# HDMI.net
KiCad netlist of a schematic drawn in Altium Designer
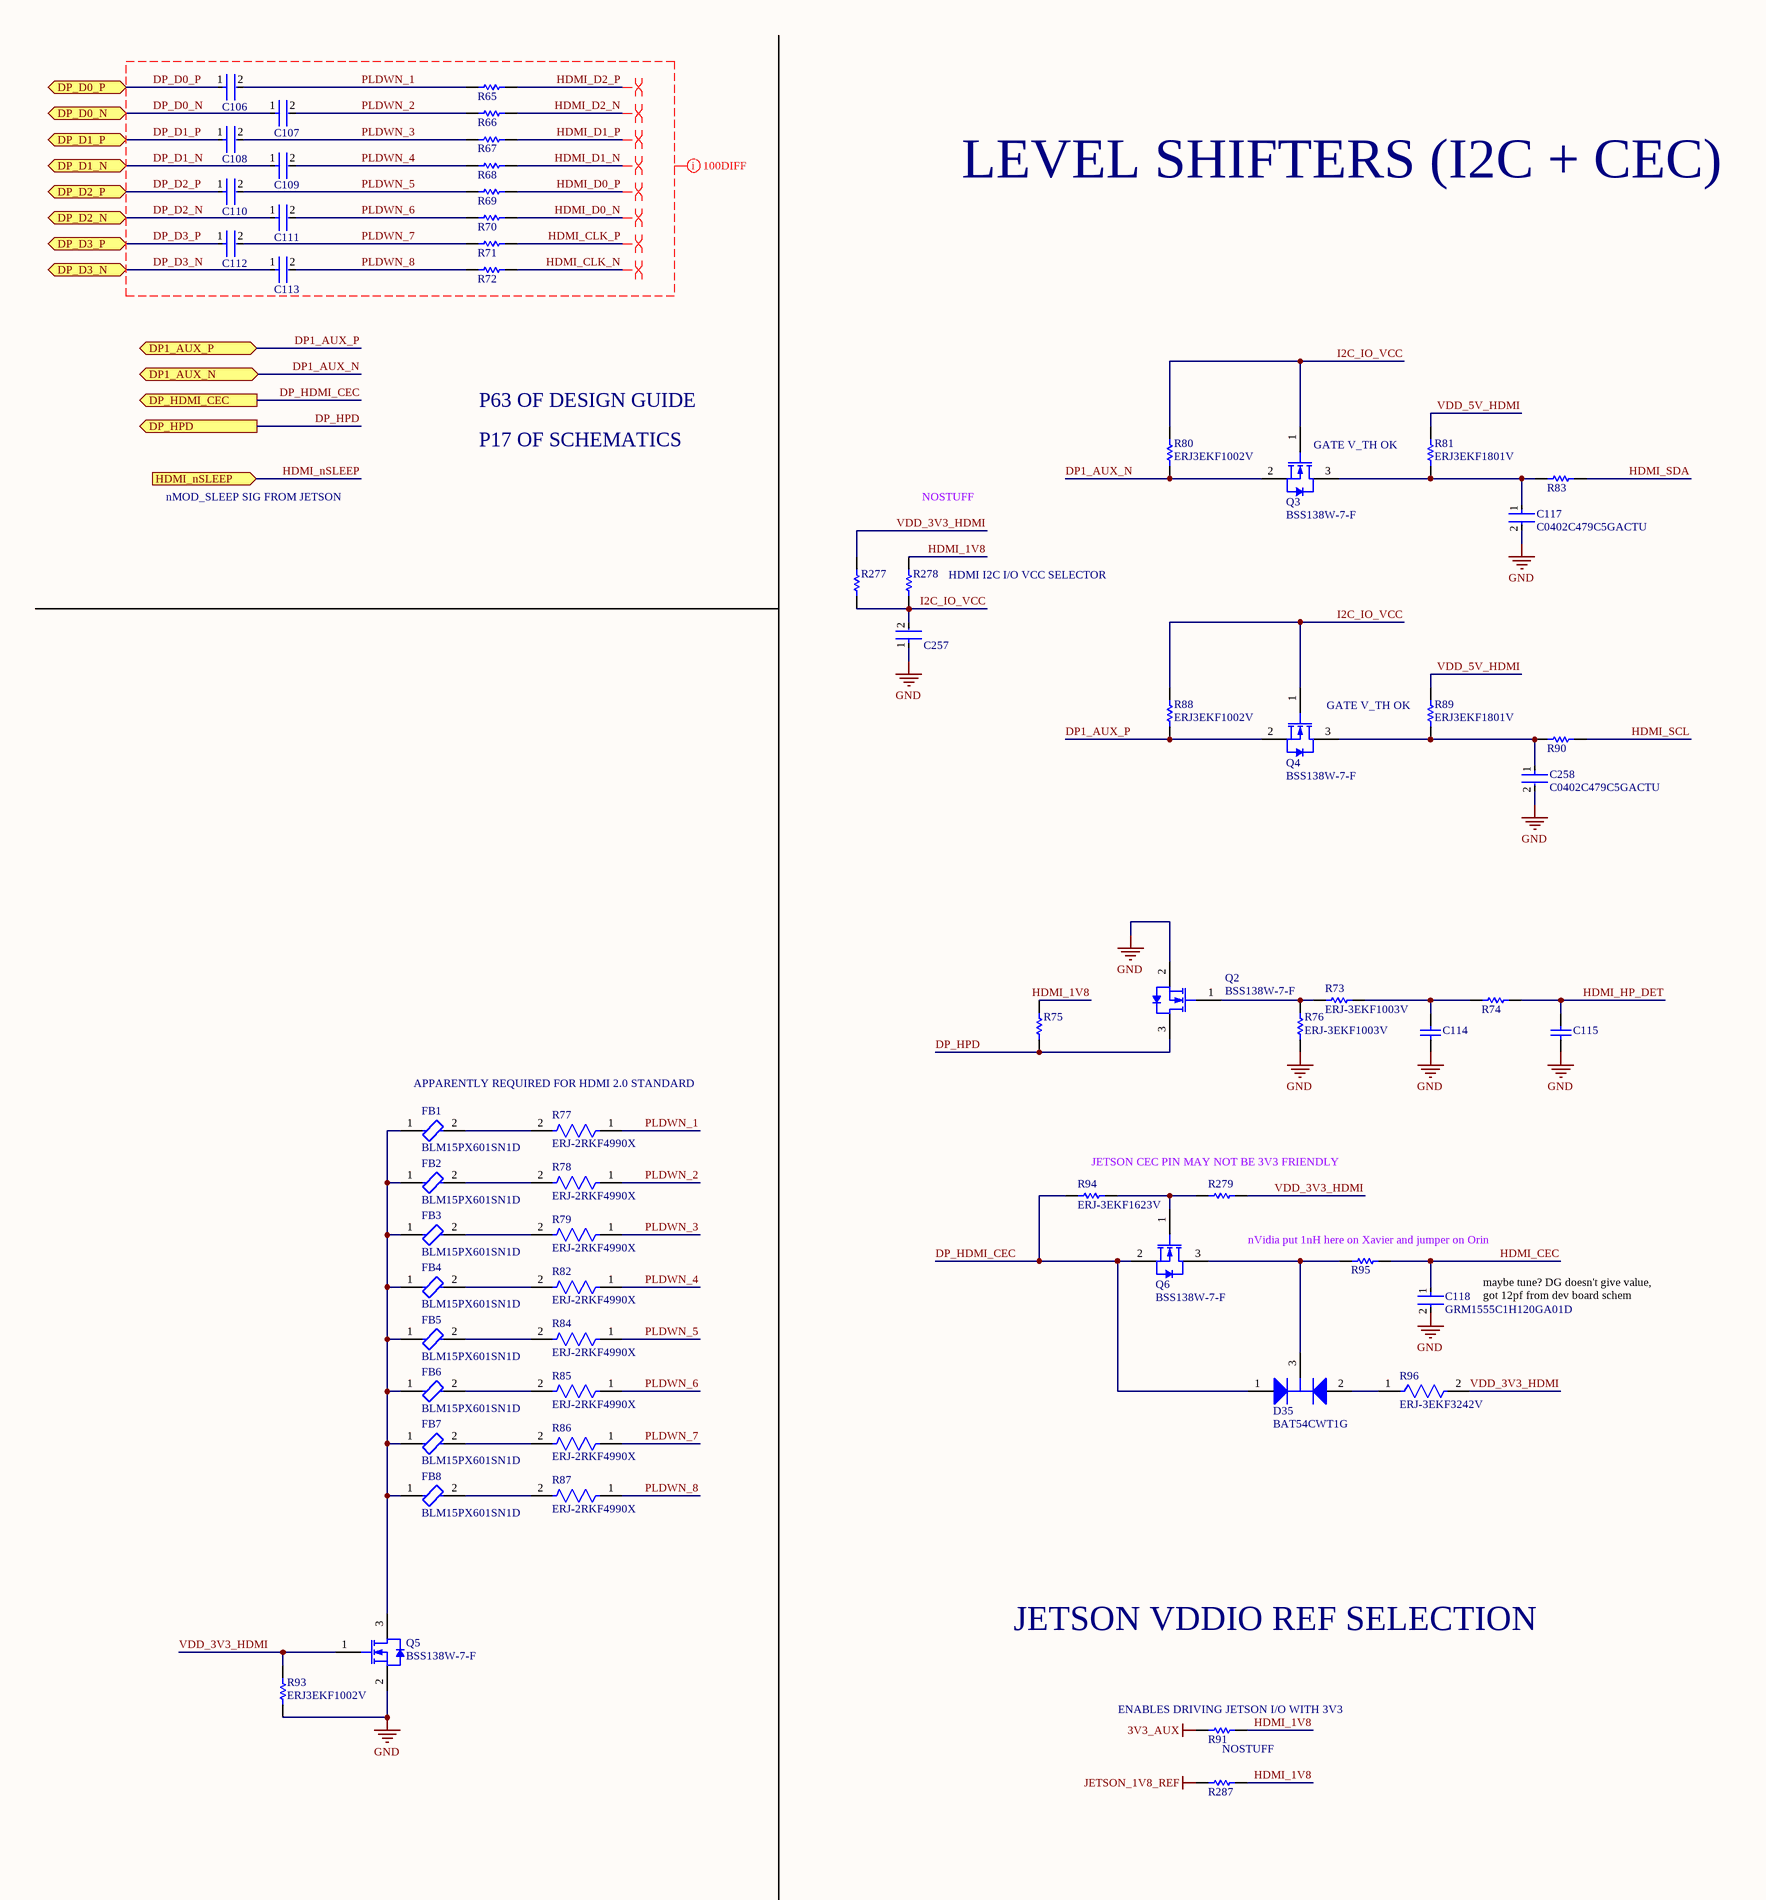
[diagram p0: HDMI.SchDoc, left]
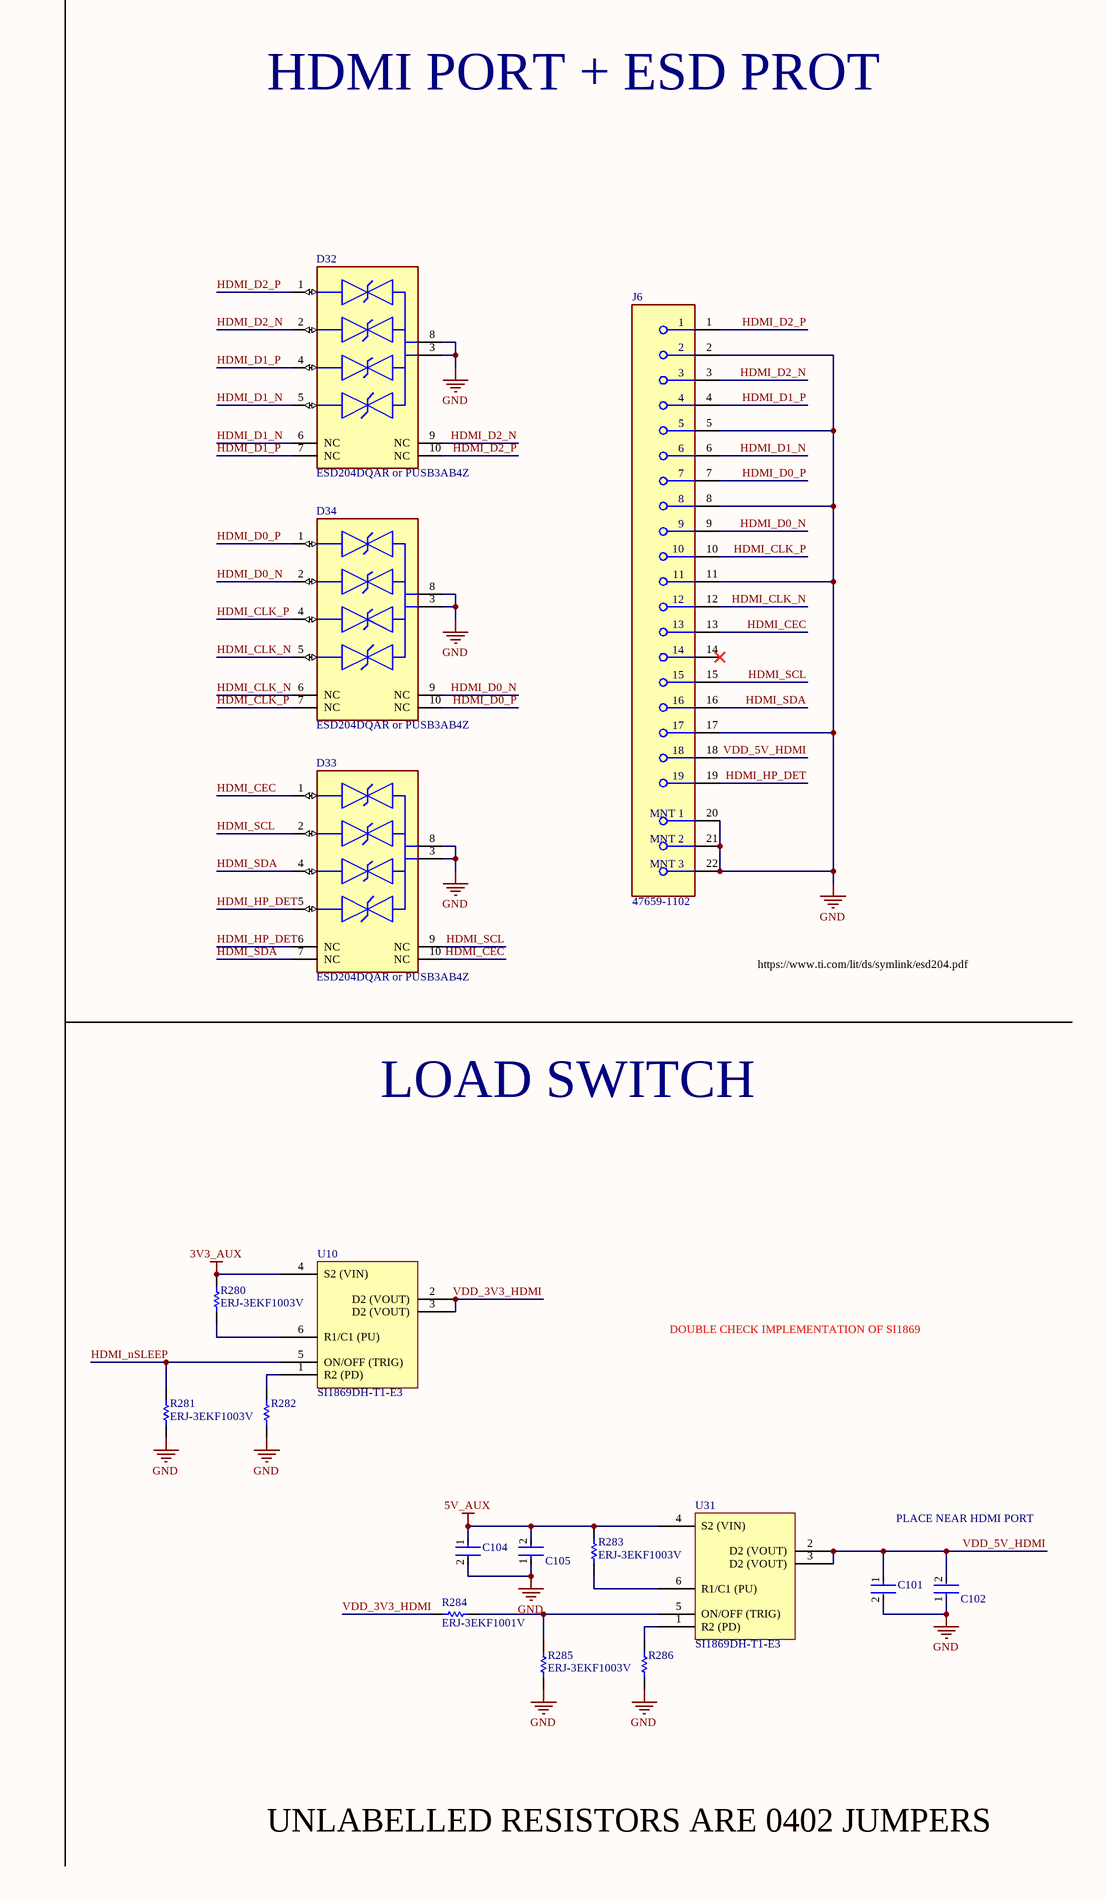
[diagram p1: HDMI.SchDoc, right]

(export (version "E")
  (design (tool "Eeschema 10.0.6"))
  (components
    (comp (ref "C101")
      (value "GRM188R60J106ME47D")
      (footprint "FP-GRM188-0_1-e0_2_0_55-IPC_A")
      (description "Chip Multilayer Ceramic Capacitors for General Purpose, 0603, 10uF, X5R, 15%, 20%, 6.3V")
      (fields (field (name "VOLTAGE") "6.3V") (field (name "TOLERANCE") "20%"))
      (libsource (lib "Altium Content Vault") (part "02cd4be3c70576c341d710602a673aa"))
    )
    (comp (ref "C102")
      (value "C1005X7R1H104K050BB")
      (footprint "FP-C1005-050-0_05-IPC_C")
      (description "Multilayer Ceramic Capacitors 100nF ±10% 50V X7R SMD 0402")
      (fields (field (name "VOLTAGE") "50V") (field (name "TOLERANCE") "10%"))
      (libsource (lib "Altium Content Vault") (part "b4654b650e69147ec39a6b967a45e02"))
    )
    (comp (ref "C104")
      (value "GRM188R60J106ME47D")
      (footprint "FP-GRM188-0_1-e0_2_0_55-IPC_A")
      (description "Chip Multilayer Ceramic Capacitors for General Purpose, 0603, 10uF, X5R, 15%, 20%, 6.3V")
      (fields (field (name "VOLTAGE") "6.3V") (field (name "TOLERANCE") "20%"))
      (libsource (lib "Altium Content Vault") (part "02cd4be3c70576c341d710602a673aa"))
    )
    (comp (ref "C105")
      (value "C1005X7R1H104K050BB")
      (footprint "FP-C1005-050-0_05-IPC_C")
      (description "Multilayer Ceramic Capacitors 100nF ±10% 50V X7R SMD 0402")
      (fields (field (name "VOLTAGE") "50V") (field (name "TOLERANCE") "10%"))
      (libsource (lib "Altium Content Vault") (part "b4654b650e69147ec39a6b967a45e02"))
    )
    (comp (ref "C106")
      (value "C1005X7R1H104K050BB")
      (footprint "FP-C1005-050-0_05-IPC_C")
      (description "Multilayer Ceramic Capacitors 100nF ±10% 50V X7R SMD 0402")
      (fields (field (name "VOLTAGE") "50V") (field (name "TOLERANCE") "10%"))
      (libsource (lib "Altium Content Vault") (part "b4654b650e69147ec39a6b967a45e02"))
    )
    (comp (ref "C107")
      (value "C1005X7R1H104K050BB")
      (footprint "FP-C1005-050-0_05-IPC_C")
      (description "Multilayer Ceramic Capacitors 100nF ±10% 50V X7R SMD 0402")
      (fields (field (name "VOLTAGE") "50V") (field (name "TOLERANCE") "10%"))
      (libsource (lib "Altium Content Vault") (part "b4654b650e69147ec39a6b967a45e02"))
    )
    (comp (ref "C108")
      (value "C1005X7R1H104K050BB")
      (footprint "FP-C1005-050-0_05-IPC_C")
      (description "Multilayer Ceramic Capacitors 100nF ±10% 50V X7R SMD 0402")
      (fields (field (name "VOLTAGE") "50V") (field (name "TOLERANCE") "10%"))
      (libsource (lib "Altium Content Vault") (part "b4654b650e69147ec39a6b967a45e02"))
    )
    (comp (ref "C109")
      (value "C1005X7R1H104K050BB")
      (footprint "FP-C1005-050-0_05-IPC_C")
      (description "Multilayer Ceramic Capacitors 100nF ±10% 50V X7R SMD 0402")
      (fields (field (name "VOLTAGE") "50V") (field (name "TOLERANCE") "10%"))
      (libsource (lib "Altium Content Vault") (part "b4654b650e69147ec39a6b967a45e02"))
    )
    (comp (ref "C110")
      (value "C1005X7R1H104K050BB")
      (footprint "FP-C1005-050-0_05-IPC_C")
      (description "Multilayer Ceramic Capacitors 100nF ±10% 50V X7R SMD 0402")
      (fields (field (name "VOLTAGE") "50V") (field (name "TOLERANCE") "10%"))
      (libsource (lib "Altium Content Vault") (part "b4654b650e69147ec39a6b967a45e02"))
    )
    (comp (ref "C111")
      (value "C1005X7R1H104K050BB")
      (footprint "FP-C1005-050-0_05-IPC_C")
      (description "Multilayer Ceramic Capacitors 100nF ±10% 50V X7R SMD 0402")
      (fields (field (name "VOLTAGE") "50V") (field (name "TOLERANCE") "10%"))
      (libsource (lib "Altium Content Vault") (part "b4654b650e69147ec39a6b967a45e02"))
    )
    (comp (ref "C112")
      (value "C1005X7R1H104K050BB")
      (footprint "FP-C1005-050-0_05-IPC_C")
      (description "Multilayer Ceramic Capacitors 100nF ±10% 50V X7R SMD 0402")
      (fields (field (name "VOLTAGE") "50V") (field (name "TOLERANCE") "10%"))
      (libsource (lib "Altium Content Vault") (part "b4654b650e69147ec39a6b967a45e02"))
    )
    (comp (ref "C113")
      (value "C1005X7R1H104K050BB")
      (footprint "FP-C1005-050-0_05-IPC_C")
      (description "Multilayer Ceramic Capacitors 100nF ±10% 50V X7R SMD 0402")
      (fields (field (name "VOLTAGE") "50V") (field (name "TOLERANCE") "10%"))
      (libsource (lib "Altium Content Vault") (part "b4654b650e69147ec39a6b967a45e02"))
    )
    (comp (ref "C114")
      (value "C0402C221K5RAC7867")
      (footprint "CAPC1005X60X30NL05T10")
      (fields (field (name "MANUFACTURER") "Kemet"))
      (libsource (lib "Altium Content Vault") (part "CAP"))
    )
    (comp (ref "C115")
      (value "C0402C221K5RAC7867")
      (footprint "CAPC1005X60X30NL05T10")
      (fields (field (name "MANUFACTURER") "Kemet"))
      (libsource (lib "Altium Content Vault") (part "CAP"))
    )
    (comp (ref "C117")
      (value "C0402C479C5GACTU")
      (footprint "FP-C0402-BB-MFG")
      (description "CAP CER 4.7PF 50V NP0 0402")
      (fields
        (field (name "TOLERANCE") "0.25 pF")
        (field (name "OCTOPART") "https://octopart.com/c0402c479c5gactu-kemet-9144199")
      )
      (libsource (lib "Altium Content Vault") (part "b4654b650e69147ec39a6b967a45e02"))
    )
    (comp (ref "C118")
      (value "GRM1555C1H120GA01D")
      (footprint "FP-GRM155-0_05-MFG")
      (description "CAP CER 12PF 50V C0G/NP0 0402")
      (fields (field (name "TOLERANCE") "2%") (field (name "VOLTAGE") "50V"))
      (libsource (lib "Altium Content Vault") (part "b4654b650e69147ec39a6b967a45e02"))
    )
    (comp (ref "C257")
      (value "C1005X7R1H104K050BB")
      (footprint "FP-C1005-050-0_05-IPC_C")
      (description "Multilayer Ceramic Capacitors 100nF ±10% 50V X7R SMD 0402")
      (fields (field (name "VOLTAGE") "50V") (field (name "TOLERANCE") "10%"))
      (libsource (lib "Altium Content Vault") (part "b4654b650e69147ec39a6b967a45e02"))
    )
    (comp (ref "C258")
      (value "C0402C479C5GACTU")
      (footprint "FP-C0402-BB-MFG")
      (description "CAP CER 4.7PF 50V NP0 0402")
      (fields
        (field (name "TOLERANCE") "0.25 pF")
        (field (name "OCTOPART") "https://octopart.com/c0402c479c5gactu-kemet-9144199")
      )
      (libsource (lib "Altium Content Vault") (part "b4654b650e69147ec39a6b967a45e02"))
    )
    (comp (ref "D32")
      (value "ESD204DQAR or PUSB3AB4Z")
      (footprint "FP-DQA0010A-MFG")
      (description "4-CHANNEL LOW-CAPACITANCE SURGE")
      (fields
        (field (name "MANUFACTURER") "Texas Instruments")
        (field (name "OCTOPART") "https://octopart.com/esd204dqar-texas+instruments-89917476")
      )
      (libsource (lib "Altium Content Vault") (part "1465e58c1818c7767b55926832f0bf5"))
    )
    (comp (ref "D33")
      (value "ESD204DQAR or PUSB3AB4Z")
      (footprint "FP-DQA0010A-MFG")
      (description "4-CHANNEL LOW-CAPACITANCE SURGE")
      (fields
        (field (name "MANUFACTURER") "Texas Instruments")
        (field (name "OCTOPART") "https://octopart.com/esd204dqar-texas+instruments-89917476")
      )
      (libsource (lib "Altium Content Vault") (part "1465e58c1818c7767b55926832f0bf5"))
    )
    (comp (ref "D34")
      (value "ESD204DQAR or PUSB3AB4Z")
      (footprint "FP-DQA0010A-MFG")
      (description "4-CHANNEL LOW-CAPACITANCE SURGE")
      (fields
        (field (name "MANUFACTURER") "Texas Instruments")
        (field (name "OCTOPART") "https://octopart.com/esd204dqar-texas+instruments-89917476")
      )
      (libsource (lib "Altium Content Vault") (part "1465e58c1818c7767b55926832f0bf5"))
    )
    (comp (ref "D35")
      (value "BAT54CWT1G")
      (footprint "ONSC-SOT-323-3-419-04_V")
      (description "Dual Series Cathode Schottky Barrier Diodes, 3-Pin SOT-323, Pb-Free, Tape and Reel")
      (fields (field (name "MANUFACTURER") "On Semiconductor"))
      (libsource (lib "Altium Content Vault") (part "ONSC-D-A1A2K3-3"))
    )
    (comp (ref "FB1")
      (value "BLM15PX601SN1D")
      (footprint "FP-BLM15-0_05-MFG")
      (description "Chip Ferrite Bead, 0402, 600Ω @ 100MHz, 0.23Ω, 25%, 900mA")
      (fields (field (name "TOLERANCE") "25%"))
      (libsource (lib "Altium Content Vault") (part "5f30dd21d616792df468990f7003faa"))
    )
    (comp (ref "FB2")
      (value "BLM15PX601SN1D")
      (footprint "FP-BLM15-0_05-MFG")
      (description "Chip Ferrite Bead, 0402, 600Ω @ 100MHz, 0.23Ω, 25%, 900mA")
      (fields (field (name "TOLERANCE") "25%"))
      (libsource (lib "Altium Content Vault") (part "5f30dd21d616792df468990f7003faa"))
    )
    (comp (ref "FB3")
      (value "BLM15PX601SN1D")
      (footprint "FP-BLM15-0_05-MFG")
      (description "Chip Ferrite Bead, 0402, 600Ω @ 100MHz, 0.23Ω, 25%, 900mA")
      (fields (field (name "TOLERANCE") "25%"))
      (libsource (lib "Altium Content Vault") (part "5f30dd21d616792df468990f7003faa"))
    )
    (comp (ref "FB4")
      (value "BLM15PX601SN1D")
      (footprint "FP-BLM15-0_05-MFG")
      (description "Chip Ferrite Bead, 0402, 600Ω @ 100MHz, 0.23Ω, 25%, 900mA")
      (fields (field (name "TOLERANCE") "25%"))
      (libsource (lib "Altium Content Vault") (part "5f30dd21d616792df468990f7003faa"))
    )
    (comp (ref "FB5")
      (value "BLM15PX601SN1D")
      (footprint "FP-BLM15-0_05-MFG")
      (description "Chip Ferrite Bead, 0402, 600Ω @ 100MHz, 0.23Ω, 25%, 900mA")
      (fields (field (name "TOLERANCE") "25%"))
      (libsource (lib "Altium Content Vault") (part "5f30dd21d616792df468990f7003faa"))
    )
    (comp (ref "FB6")
      (value "BLM15PX601SN1D")
      (footprint "FP-BLM15-0_05-MFG")
      (description "Chip Ferrite Bead, 0402, 600Ω @ 100MHz, 0.23Ω, 25%, 900mA")
      (fields (field (name "TOLERANCE") "25%"))
      (libsource (lib "Altium Content Vault") (part "5f30dd21d616792df468990f7003faa"))
    )
    (comp (ref "FB7")
      (value "BLM15PX601SN1D")
      (footprint "FP-BLM15-0_05-MFG")
      (description "Chip Ferrite Bead, 0402, 600Ω @ 100MHz, 0.23Ω, 25%, 900mA")
      (fields (field (name "TOLERANCE") "25%"))
      (libsource (lib "Altium Content Vault") (part "5f30dd21d616792df468990f7003faa"))
    )
    (comp (ref "FB8")
      (value "BLM15PX601SN1D")
      (footprint "FP-BLM15-0_05-MFG")
      (description "Chip Ferrite Bead, 0402, 600Ω @ 100MHz, 0.23Ω, 25%, 900mA")
      (fields (field (name "TOLERANCE") "25%"))
      (libsource (lib "Altium Content Vault") (part "5f30dd21d616792df468990f7003faa"))
    )
    (comp (ref "J6")
      (value "47659-1102")
      (footprint "FP-47659-1102-MFG")
      (description "HDMI REC.VERTICAL SMT TYPE W/HEI")
      (libsource (lib "Altium Content Vault") (part "60e05bcc1364a128ef07df4509dd673"))
    )
    (comp (ref "Q2")
      (value "BSS138W-7-F")
      (footprint "DIOD-SOT323-3_V")
      (fields (field (name "MANUFACTURER") "DiodesIncorporated"))
      (libsource (lib "Altium Content Vault") (part "NEMOS-GSD-3"))
    )
    (comp (ref "Q3")
      (value "BSS138W-7-F")
      (footprint "DIOD-SOT323-3_V")
      (fields (field (name "MANUFACTURER") "DiodesIncorporated"))
      (libsource (lib "Altium Content Vault") (part "NEMOS-GSD-3"))
    )
    (comp (ref "Q4")
      (value "BSS138W-7-F")
      (footprint "DIOD-SOT323-3_V")
      (fields (field (name "MANUFACTURER") "DiodesIncorporated"))
      (libsource (lib "Altium Content Vault") (part "NEMOS-GSD-3"))
    )
    (comp (ref "Q5")
      (value "BSS138W-7-F")
      (footprint "DIOD-SOT323-3_V")
      (fields (field (name "MANUFACTURER") "DiodesIncorporated"))
      (libsource (lib "Altium Content Vault") (part "NEMOS-GSD-3"))
    )
    (comp (ref "Q6")
      (value "BSS138W-7-F")
      (footprint "DIOD-SOT323-3_V")
      (fields (field (name "MANUFACTURER") "DiodesIncorporated"))
      (libsource (lib "Altium Content Vault") (part "NEMOS-GSD-3"))
    )
    (comp (ref "R65")
      (value "0402 JUMPER")
      (footprint "RESC1005X40X25ML05T05")
      (description "READ THE NAME")
      (libsource (lib "Space Concordia") (part "CMP-009-00206-2"))
    )
    (comp (ref "R66")
      (value "0402 JUMPER")
      (footprint "RESC1005X40X25ML05T05")
      (description "READ THE NAME")
      (libsource (lib "Space Concordia") (part "CMP-009-00206-2"))
    )
    (comp (ref "R67")
      (value "0402 JUMPER")
      (footprint "RESC1005X40X25ML05T05")
      (description "READ THE NAME")
      (libsource (lib "Space Concordia") (part "CMP-009-00206-2"))
    )
    (comp (ref "R68")
      (value "0402 JUMPER")
      (footprint "RESC1005X40X25ML05T05")
      (description "READ THE NAME")
      (libsource (lib "Space Concordia") (part "CMP-009-00206-2"))
    )
    (comp (ref "R69")
      (value "0402 JUMPER")
      (footprint "RESC1005X40X25ML05T05")
      (description "READ THE NAME")
      (libsource (lib "Space Concordia") (part "CMP-009-00206-2"))
    )
    (comp (ref "R70")
      (value "0402 JUMPER")
      (footprint "RESC1005X40X25ML05T05")
      (description "READ THE NAME")
      (libsource (lib "Space Concordia") (part "CMP-009-00206-2"))
    )
    (comp (ref "R71")
      (value "0402 JUMPER")
      (footprint "RESC1005X40X25ML05T05")
      (description "READ THE NAME")
      (libsource (lib "Space Concordia") (part "CMP-009-00206-2"))
    )
    (comp (ref "R72")
      (value "0402 JUMPER")
      (footprint "RESC1005X40X25ML05T05")
      (description "READ THE NAME")
      (libsource (lib "Space Concordia") (part "CMP-009-00206-2"))
    )
    (comp (ref "R73")
      (value "ERJ-3EKF1003V")
      (footprint "RESC1608X55X30ML15T15")
      (fields (field (name "MANUFACTURER") "Panasonic"))
      (libsource (lib "Altium Content Vault") (part "RES"))
    )
    (comp (ref "R74")
      (value "0402 JUMPER")
      (footprint "RESC1005X40X25ML05T05")
      (description "READ THE NAME")
      (libsource (lib "Space Concordia") (part "CMP-009-00206-2"))
    )
    (comp (ref "R75")
      (value "ERJ3EKF1002V")
      (footprint "RESC1609X55X30LL15T15")
      (description "Chip Resistor, 10 KOhm, +/- 1%, 0.1 W, -55 to 155 degC, 0603 (1608 Metric), RoHS, Tape and Reel")
      (fields (field (name "TOLERANCE") "1%") (field (name "MANUFACTURER") "Panasonic"))
      (libsource (lib "Altium Content Vault") (part "RES-2"))
    )
    (comp (ref "R76")
      (value "ERJ-3EKF1003V")
      (footprint "RESC1608X55X30ML15T15")
      (fields (field (name "MANUFACTURER") "Panasonic"))
      (libsource (lib "Altium Content Vault") (part "RES"))
    )
    (comp (ref "R77")
      (value "ERJ-2RKF4990X")
      (footprint "FP-ERJ2RK-MFG")
      (description "RES SMD 499 OHM 1% 1/10W 0402")
      (fields (field (name "TOLERANCE") "1%"))
      (libsource (lib "Altium Content Vault") (part "1029c3af85768c4190bb7ad29bc67b5"))
    )
    (comp (ref "R78")
      (value "ERJ-2RKF4990X")
      (footprint "FP-ERJ2RK-MFG")
      (description "RES SMD 499 OHM 1% 1/10W 0402")
      (fields (field (name "TOLERANCE") "1%"))
      (libsource (lib "Altium Content Vault") (part "1029c3af85768c4190bb7ad29bc67b5"))
    )
    (comp (ref "R79")
      (value "ERJ-2RKF4990X")
      (footprint "FP-ERJ2RK-MFG")
      (description "RES SMD 499 OHM 1% 1/10W 0402")
      (fields (field (name "TOLERANCE") "1%"))
      (libsource (lib "Altium Content Vault") (part "1029c3af85768c4190bb7ad29bc67b5"))
    )
    (comp (ref "R80")
      (value "ERJ3EKF1002V")
      (footprint "RESC1609X55X30LL15T15")
      (description "Chip Resistor, 10 KOhm, +/- 1%, 0.1 W, -55 to 155 degC, 0603 (1608 Metric), RoHS, Tape and Reel")
      (fields (field (name "TOLERANCE") "1%") (field (name "MANUFACTURER") "Panasonic"))
      (libsource (lib "Altium Content Vault") (part "RES-2"))
    )
    (comp (ref "R81")
      (value "ERJ3EKF1801V")
      (footprint "RESC1608X55X30LL15T15")
      (description "MODIFIED P/N")
      (fields (field (name "MANUFACTURER") "Panasonic") (field (name "PART NUMBER") "ERJ3EKF2701V"))
      (libsource (lib "Altium Content Vault") (part "RES"))
    )
    (comp (ref "R82")
      (value "ERJ-2RKF4990X")
      (footprint "FP-ERJ2RK-MFG")
      (description "RES SMD 499 OHM 1% 1/10W 0402")
      (fields (field (name "TOLERANCE") "1%"))
      (libsource (lib "Altium Content Vault") (part "1029c3af85768c4190bb7ad29bc67b5"))
    )
    (comp (ref "R83")
      (value "0402 JUMPER")
      (footprint "RESC1005X40X25ML05T05")
      (description "READ THE NAME")
      (libsource (lib "Space Concordia") (part "CMP-009-00206-2"))
    )
    (comp (ref "R84")
      (value "ERJ-2RKF4990X")
      (footprint "FP-ERJ2RK-MFG")
      (description "RES SMD 499 OHM 1% 1/10W 0402")
      (fields (field (name "TOLERANCE") "1%"))
      (libsource (lib "Altium Content Vault") (part "1029c3af85768c4190bb7ad29bc67b5"))
    )
    (comp (ref "R85")
      (value "ERJ-2RKF4990X")
      (footprint "FP-ERJ2RK-MFG")
      (description "RES SMD 499 OHM 1% 1/10W 0402")
      (fields (field (name "TOLERANCE") "1%"))
      (libsource (lib "Altium Content Vault") (part "1029c3af85768c4190bb7ad29bc67b5"))
    )
    (comp (ref "R86")
      (value "ERJ-2RKF4990X")
      (footprint "FP-ERJ2RK-MFG")
      (description "RES SMD 499 OHM 1% 1/10W 0402")
      (fields (field (name "TOLERANCE") "1%"))
      (libsource (lib "Altium Content Vault") (part "1029c3af85768c4190bb7ad29bc67b5"))
    )
    (comp (ref "R87")
      (value "ERJ-2RKF4990X")
      (footprint "FP-ERJ2RK-MFG")
      (description "RES SMD 499 OHM 1% 1/10W 0402")
      (fields (field (name "TOLERANCE") "1%"))
      (libsource (lib "Altium Content Vault") (part "1029c3af85768c4190bb7ad29bc67b5"))
    )
    (comp (ref "R88")
      (value "ERJ3EKF1002V")
      (footprint "RESC1609X55X30LL15T15")
      (description "Chip Resistor, 10 KOhm, +/- 1%, 0.1 W, -55 to 155 degC, 0603 (1608 Metric), RoHS, Tape and Reel")
      (fields (field (name "TOLERANCE") "1%") (field (name "MANUFACTURER") "Panasonic"))
      (libsource (lib "Altium Content Vault") (part "RES-2"))
    )
    (comp (ref "R89")
      (value "ERJ3EKF1801V")
      (footprint "RESC1608X55X30LL15T15")
      (description "MODIFIED P/N")
      (fields (field (name "MANUFACTURER") "Panasonic") (field (name "PART NUMBER") "ERJ3EKF2701V"))
      (libsource (lib "Altium Content Vault") (part "RES"))
    )
    (comp (ref "R90")
      (value "0402 JUMPER")
      (footprint "RESC1005X40X25ML05T05")
      (description "READ THE NAME")
      (libsource (lib "Space Concordia") (part "CMP-009-00206-2"))
    )
    (comp (ref "R91")
      (value "0402 JUMPER")
      (footprint "RESC1005X40X25ML05T05")
      (description "READ THE NAME")
      (libsource (lib "Space Concordia") (part "CMP-009-00206-2"))
    )
    (comp (ref "R93")
      (value "ERJ3EKF1002V")
      (footprint "RESC1609X55X30LL15T15")
      (description "Chip Resistor, 10 KOhm, +/- 1%, 0.1 W, -55 to 155 degC, 0603 (1608 Metric), RoHS, Tape and Reel")
      (fields (field (name "TOLERANCE") "1%") (field (name "MANUFACTURER") "Panasonic"))
      (libsource (lib "Altium Content Vault") (part "RES-2"))
    )
    (comp (ref "R94")
      (value "ERJ-3EKF1623V")
      (footprint "RESC1608X55X30ML15T15")
      (fields (field (name "MANUFACTURER") "Panasonic"))
      (libsource (lib "Altium Content Vault") (part "RES"))
    )
    (comp (ref "R95")
      (value "0402 JUMPER")
      (footprint "RESC1005X40X25ML05T05")
      (description "READ THE NAME")
      (libsource (lib "Space Concordia") (part "CMP-009-00206-2"))
    )
    (comp (ref "R96")
      (value "ERJ-3EKF3242V")
      (footprint "FP-ERJ3EK-MFG")
      (description "RES SMD 32.4K OHM 1% 1/10W 0603")
      (fields (field (name "TOLERANCE") "1%"))
      (libsource (lib "Altium Content Vault") (part "1029c3af85768c4190bb7ad29bc67b5"))
    )
    (comp (ref "R277")
      (value "0402 JUMPER")
      (footprint "RESC1005X40X25ML05T05")
      (description "READ THE NAME")
      (libsource (lib "Space Concordia") (part "CMP-009-00206-2"))
    )
    (comp (ref "R278")
      (value "0402 JUMPER")
      (footprint "RESC1005X40X25ML05T05")
      (description "READ THE NAME")
      (libsource (lib "Space Concordia") (part "CMP-009-00206-2"))
    )
    (comp (ref "R279")
      (value "0402 JUMPER")
      (footprint "RESC1005X40X25ML05T05")
      (description "READ THE NAME")
      (libsource (lib "Space Concordia") (part "CMP-009-00206-2"))
    )
    (comp (ref "R280")
      (value "ERJ-3EKF1003V")
      (footprint "RESC1608X55X30ML15T15")
      (fields (field (name "MANUFACTURER") "Panasonic"))
      (libsource (lib "Altium Content Vault") (part "RES"))
    )
    (comp (ref "R281")
      (value "ERJ-3EKF1003V")
      (footprint "RESC1608X55X30ML15T15")
      (fields (field (name "MANUFACTURER") "Panasonic"))
      (libsource (lib "Altium Content Vault") (part "RES"))
    )
    (comp (ref "R282")
      (value "0402 JUMPER")
      (footprint "RESC1005X40X25ML05T05")
      (description "READ THE NAME")
      (libsource (lib "Space Concordia") (part "CMP-009-00206-2"))
    )
    (comp (ref "R283")
      (value "ERJ-3EKF1003V")
      (footprint "RESC1608X55X30ML15T15")
      (fields (field (name "MANUFACTURER") "Panasonic"))
      (libsource (lib "Altium Content Vault") (part "RES"))
    )
    (comp (ref "R284")
      (value "ERJ-3EKF1001V")
      (footprint "RESC1608X55X30LL15T15")
      (fields (field (name "MANUFACTURER") "Panasonic"))
      (libsource (lib "Altium Content Vault") (part "RES"))
    )
    (comp (ref "R285")
      (value "ERJ-3EKF1003V")
      (footprint "RESC1608X55X30ML15T15")
      (fields (field (name "MANUFACTURER") "Panasonic"))
      (libsource (lib "Altium Content Vault") (part "RES"))
    )
    (comp (ref "R286")
      (value "0402 JUMPER")
      (footprint "RESC1005X40X25ML05T05")
      (description "READ THE NAME")
      (libsource (lib "Space Concordia") (part "CMP-009-00206-2"))
    )
    (comp (ref "R287")
      (value "0402 JUMPER")
      (footprint "RESC1005X40X25ML05T05")
      (description "READ THE NAME")
      (libsource (lib "Space Concordia") (part "CMP-009-00206-2"))
    )
    (comp (ref "U10")
      (value "SI1869DH-T1-E3")
      (footprint "SOT65P242X110-6N")
      (description "Power Supply Support Circuit, Adjustable, 1 Channel, PDSO6")
      (libsource (lib "Space Concordia") (part "SI1869DH-T1-E3"))
    )
    (comp (ref "U31")
      (value "SI1869DH-T1-E3")
      (footprint "SOT65P242X110-6N")
      (description "Power Supply Support Circuit, Adjustable, 1 Channel, PDSO6")
      (libsource (lib "Space Concordia") (part "SI1869DH-T1-E3"))
    )
  )
  (nets
    (net (code "1") (name "/DP1_AUX_N") (class "Default")
      (node (ref "Q3") (pin "2") (pinfunction "S_2") (pintype "passive"))
      (node (ref "R80") (pin "1") (pinfunction "1_1") (pintype "passive"))
    )
    (net (code "2") (name "/DP1_AUX_P") (class "Default")
      (node (ref "Q4") (pin "2") (pinfunction "S_2") (pintype "passive"))
      (node (ref "R88") (pin "1") (pinfunction "1_1") (pintype "passive"))
    )
    (net (code "3") (name "/DP_D0_N") (class "Default")
      (node (ref "C107") (pin "1") (pinfunction "1_1") (pintype "passive"))
    )
    (net (code "4") (name "/DP_D0_P") (class "Default")
      (node (ref "C106") (pin "1") (pinfunction "1_1") (pintype "passive"))
    )
    (net (code "5") (name "/DP_D1_N") (class "Default")
      (node (ref "C109") (pin "1") (pinfunction "1_1") (pintype "passive"))
    )
    (net (code "6") (name "/DP_D1_P") (class "Default")
      (node (ref "C108") (pin "1") (pinfunction "1_1") (pintype "passive"))
    )
    (net (code "7") (name "/DP_D2_N") (class "Default")
      (node (ref "C111") (pin "1") (pinfunction "1_1") (pintype "passive"))
    )
    (net (code "8") (name "/DP_D2_P") (class "Default")
      (node (ref "C110") (pin "1") (pinfunction "1_1") (pintype "passive"))
    )
    (net (code "9") (name "/DP_D3_N") (class "Default")
      (node (ref "C113") (pin "1") (pinfunction "1_1") (pintype "passive"))
    )
    (net (code "10") (name "/DP_D3_P") (class "Default")
      (node (ref "C112") (pin "1") (pinfunction "1_1") (pintype "passive"))
    )
    (net (code "11") (name "/DP_HDMI_CEC") (class "Default")
      (node (ref "D35") (pin "1") (pinfunction "A1_1") (pintype "passive"))
      (node (ref "Q6") (pin "2") (pinfunction "S_2") (pintype "passive"))
      (node (ref "R94") (pin "1") (pinfunction "1_1") (pintype "passive"))
    )
    (net (code "12") (name "/DP_HPD") (class "Default")
      (node (ref "Q2") (pin "3") (pinfunction "D_3") (pintype "passive"))
      (node (ref "R75") (pin "1") (pinfunction "1_1") (pintype "passive"))
    )
    (net (code "13") (name "/HDMI_1V8") (class "Default")
      (node (ref "R278") (pin "2") (pinfunction "2_2") (pintype "passive"))
      (node (ref "R287") (pin "2") (pinfunction "2_2") (pintype "passive"))
      (node (ref "R75") (pin "2") (pinfunction "2_2") (pintype "passive"))
      (node (ref "R91") (pin "2") (pinfunction "2_2") (pintype "passive"))
    )
    (net (code "14") (name "/HDMI_CEC") (class "Default")
      (node (ref "C118") (pin "1") (pinfunction "1_1") (pintype "passive"))
      (node (ref "D33") (pin "1") (pinfunction "IO1_1") (pintype "bidirectional"))
      (node (ref "D33") (pin "10") (pinfunction "NC_10") (pintype "passive"))
      (node (ref "J6") (pin "13") (pinfunction "13_13") (pintype "passive"))
      (node (ref "R95") (pin "2") (pinfunction "2_2") (pintype "passive"))
    )
    (net (code "15") (name "/HDMI_CLK_N") (class "Default")
      (node (ref "D34") (pin "5") (pinfunction "IO4_5") (pintype "bidirectional"))
      (node (ref "D34") (pin "6") (pinfunction "NC_6") (pintype "passive"))
      (node (ref "J6") (pin "12") (pinfunction "12_12") (pintype "passive"))
      (node (ref "R72") (pin "2") (pinfunction "2_2") (pintype "passive"))
    )
    (net (code "16") (name "/HDMI_CLK_P") (class "Default")
      (node (ref "D34") (pin "4") (pinfunction "IO3_4") (pintype "bidirectional"))
      (node (ref "D34") (pin "7") (pinfunction "NC_7") (pintype "passive"))
      (node (ref "J6") (pin "10") (pinfunction "10_10") (pintype "passive"))
      (node (ref "R71") (pin "2") (pinfunction "2_2") (pintype "passive"))
    )
    (net (code "17") (name "/HDMI_D0_N") (class "Default")
      (node (ref "D34") (pin "2") (pinfunction "IO2_2") (pintype "bidirectional"))
      (node (ref "D34") (pin "9") (pinfunction "NC_9") (pintype "passive"))
      (node (ref "J6") (pin "9") (pinfunction "9_9") (pintype "passive"))
      (node (ref "R70") (pin "2") (pinfunction "2_2") (pintype "passive"))
    )
    (net (code "18") (name "/HDMI_D0_P") (class "Default")
      (node (ref "D34") (pin "1") (pinfunction "IO1_1") (pintype "bidirectional"))
      (node (ref "D34") (pin "10") (pinfunction "NC_10") (pintype "passive"))
      (node (ref "J6") (pin "7") (pinfunction "7_7") (pintype "passive"))
      (node (ref "R69") (pin "2") (pinfunction "2_2") (pintype "passive"))
    )
    (net (code "19") (name "/HDMI_D1_N") (class "Default")
      (node (ref "D32") (pin "5") (pinfunction "IO4_5") (pintype "bidirectional"))
      (node (ref "D32") (pin "6") (pinfunction "NC_6") (pintype "passive"))
      (node (ref "J6") (pin "6") (pinfunction "6_6") (pintype "passive"))
      (node (ref "R68") (pin "2") (pinfunction "2_2") (pintype "passive"))
    )
    (net (code "20") (name "/HDMI_D1_P") (class "Default")
      (node (ref "D32") (pin "4") (pinfunction "IO3_4") (pintype "bidirectional"))
      (node (ref "D32") (pin "7") (pinfunction "NC_7") (pintype "passive"))
      (node (ref "J6") (pin "4") (pinfunction "4_4") (pintype "passive"))
      (node (ref "R67") (pin "2") (pinfunction "2_2") (pintype "passive"))
    )
    (net (code "21") (name "/HDMI_D2_N") (class "Default")
      (node (ref "D32") (pin "2") (pinfunction "IO2_2") (pintype "bidirectional"))
      (node (ref "D32") (pin "9") (pinfunction "NC_9") (pintype "passive"))
      (node (ref "J6") (pin "3") (pinfunction "3_3") (pintype "passive"))
      (node (ref "R66") (pin "2") (pinfunction "2_2") (pintype "passive"))
    )
    (net (code "22") (name "/HDMI_D2_P") (class "Default")
      (node (ref "D32") (pin "1") (pinfunction "IO1_1") (pintype "bidirectional"))
      (node (ref "D32") (pin "10") (pinfunction "NC_10") (pintype "passive"))
      (node (ref "J6") (pin "1") (pinfunction "1_1") (pintype "passive"))
      (node (ref "R65") (pin "2") (pinfunction "2_2") (pintype "passive"))
    )
    (net (code "23") (name "/HDMI_HP_DET") (class "Default")
      (node (ref "C115") (pin "2") (pinfunction "2_2") (pintype "passive"))
      (node (ref "D33") (pin "5") (pinfunction "IO4_5") (pintype "bidirectional"))
      (node (ref "D33") (pin "6") (pinfunction "NC_6") (pintype "passive"))
      (node (ref "J6") (pin "19") (pinfunction "19_19") (pintype "passive"))
      (node (ref "R74") (pin "2") (pinfunction "2_2") (pintype "passive"))
    )
    (net (code "24") (name "/HDMI_SCL") (class "Default")
      (node (ref "D33") (pin "2") (pinfunction "IO2_2") (pintype "bidirectional"))
      (node (ref "D33") (pin "9") (pinfunction "NC_9") (pintype "passive"))
      (node (ref "J6") (pin "15") (pinfunction "15_15") (pintype "passive"))
      (node (ref "R90") (pin "2") (pinfunction "2_2") (pintype "passive"))
    )
    (net (code "25") (name "/HDMI_SDA") (class "Default")
      (node (ref "D33") (pin "4") (pinfunction "IO3_4") (pintype "bidirectional"))
      (node (ref "D33") (pin "7") (pinfunction "NC_7") (pintype "passive"))
      (node (ref "J6") (pin "16") (pinfunction "16_16") (pintype "passive"))
      (node (ref "R83") (pin "2") (pinfunction "2_2") (pintype "passive"))
    )
    (net (code "26") (name "/HDMI_nSLEEP") (class "Default")
      (node (ref "R281") (pin "2") (pinfunction "2_2") (pintype "passive"))
      (node (ref "U10") (pin "5") (pinfunction "ON/OFF_(TRIG)_5") (pintype "passive"))
    )
    (net (code "27") (name "/I2C_IO_VCC") (class "Default")
      (node (ref "C257") (pin "2") (pinfunction "2_2") (pintype "passive"))
      (node (ref "Q3") (pin "1") (pinfunction "G_1") (pintype "passive"))
      (node (ref "Q4") (pin "1") (pinfunction "G_1") (pintype "passive"))
      (node (ref "R277") (pin "1") (pinfunction "1_1") (pintype "passive"))
      (node (ref "R278") (pin "1") (pinfunction "1_1") (pintype "passive"))
      (node (ref "R80") (pin "2") (pinfunction "2_2") (pintype "passive"))
      (node (ref "R88") (pin "2") (pinfunction "2_2") (pintype "passive"))
    )
    (net (code "28") (name "/PLDWN_1") (class "Default")
      (node (ref "C106") (pin "2") (pinfunction "2_2") (pintype "passive"))
      (node (ref "R65") (pin "1") (pinfunction "1_1") (pintype "passive"))
      (node (ref "R77") (pin "1") (pinfunction "1_1") (pintype "passive"))
    )
    (net (code "29") (name "/PLDWN_2") (class "Default")
      (node (ref "C107") (pin "2") (pinfunction "2_2") (pintype "passive"))
      (node (ref "R66") (pin "1") (pinfunction "1_1") (pintype "passive"))
      (node (ref "R78") (pin "1") (pinfunction "1_1") (pintype "passive"))
    )
    (net (code "30") (name "/PLDWN_3") (class "Default")
      (node (ref "C108") (pin "2") (pinfunction "2_2") (pintype "passive"))
      (node (ref "R67") (pin "1") (pinfunction "1_1") (pintype "passive"))
      (node (ref "R79") (pin "1") (pinfunction "1_1") (pintype "passive"))
    )
    (net (code "31") (name "/PLDWN_4") (class "Default")
      (node (ref "C109") (pin "2") (pinfunction "2_2") (pintype "passive"))
      (node (ref "R68") (pin "1") (pinfunction "1_1") (pintype "passive"))
      (node (ref "R82") (pin "1") (pinfunction "1_1") (pintype "passive"))
    )
    (net (code "32") (name "/PLDWN_5") (class "Default")
      (node (ref "C110") (pin "2") (pinfunction "2_2") (pintype "passive"))
      (node (ref "R69") (pin "1") (pinfunction "1_1") (pintype "passive"))
      (node (ref "R84") (pin "1") (pinfunction "1_1") (pintype "passive"))
    )
    (net (code "33") (name "/PLDWN_6") (class "Default")
      (node (ref "C111") (pin "2") (pinfunction "2_2") (pintype "passive"))
      (node (ref "R70") (pin "1") (pinfunction "1_1") (pintype "passive"))
      (node (ref "R85") (pin "1") (pinfunction "1_1") (pintype "passive"))
    )
    (net (code "34") (name "/PLDWN_7") (class "Default")
      (node (ref "C112") (pin "2") (pinfunction "2_2") (pintype "passive"))
      (node (ref "R71") (pin "1") (pinfunction "1_1") (pintype "passive"))
      (node (ref "R86") (pin "1") (pinfunction "1_1") (pintype "passive"))
    )
    (net (code "35") (name "/PLDWN_8") (class "Default")
      (node (ref "C113") (pin "2") (pinfunction "2_2") (pintype "passive"))
      (node (ref "R72") (pin "1") (pinfunction "1_1") (pintype "passive"))
      (node (ref "R87") (pin "1") (pinfunction "1_1") (pintype "passive"))
    )
    (net (code "36") (name "/VDD_3V3_HDMI") (class "Default")
      (node (ref "Q5") (pin "1") (pinfunction "G_1") (pintype "passive"))
      (node (ref "R277") (pin "2") (pinfunction "2_2") (pintype "passive"))
      (node (ref "R279") (pin "1") (pinfunction "1_1") (pintype "passive"))
      (node (ref "R284") (pin "1") (pinfunction "1_1") (pintype "passive"))
      (node (ref "R93") (pin "2") (pinfunction "2_2") (pintype "passive"))
      (node (ref "R96") (pin "2") (pinfunction "2_2") (pintype "passive"))
      (node (ref "U10") (pin "2") (pinfunction "D2_(VOUT)_2") (pintype "passive"))
      (node (ref "U10") (pin "3") (pinfunction "D2_(VOUT)_3") (pintype "passive"))
    )
    (net (code "37") (name "/VDD_5V_HDMI") (class "Default")
      (node (ref "C101") (pin "1") (pinfunction "1_1") (pintype "passive"))
      (node (ref "C102") (pin "2") (pinfunction "2_2") (pintype "passive"))
      (node (ref "J6") (pin "18") (pinfunction "18_18") (pintype "passive"))
      (node (ref "R81") (pin "2") (pinfunction "2_2") (pintype "passive"))
      (node (ref "R89") (pin "2") (pinfunction "2_2") (pintype "passive"))
      (node (ref "U31") (pin "2") (pinfunction "D2_(VOUT)_2") (pintype "passive"))
      (node (ref "U31") (pin "3") (pinfunction "D2_(VOUT)_3") (pintype "passive"))
    )
    (net (code "38") (name "3V3_AUX") (class "Default")
      (node (ref "R280") (pin "2") (pinfunction "2_2") (pintype "passive"))
      (node (ref "R91") (pin "1") (pinfunction "1_1") (pintype "passive"))
      (node (ref "U10") (pin "4") (pinfunction "S2_(VIN)_4") (pintype "passive"))
    )
    (net (code "39") (name "5V_AUX") (class "Default")
      (node (ref "C104") (pin "1") (pinfunction "1_1") (pintype "passive"))
      (node (ref "C105") (pin "2") (pinfunction "2_2") (pintype "passive"))
      (node (ref "R283") (pin "2") (pinfunction "2_2") (pintype "passive"))
      (node (ref "U31") (pin "4") (pinfunction "S2_(VIN)_4") (pintype "passive"))
    )
    (net (code "40") (name "GND") (class "Default")
      (node (ref "C101") (pin "2") (pinfunction "2_2") (pintype "passive"))
      (node (ref "C102") (pin "1") (pinfunction "1_1") (pintype "passive"))
      (node (ref "C104") (pin "2") (pinfunction "2_2") (pintype "passive"))
      (node (ref "C105") (pin "1") (pinfunction "1_1") (pintype "passive"))
      (node (ref "C114") (pin "1") (pinfunction "1_1") (pintype "passive"))
      (node (ref "C115") (pin "1") (pinfunction "1_1") (pintype "passive"))
      (node (ref "C117") (pin "2") (pinfunction "2_2") (pintype "passive"))
      (node (ref "C118") (pin "2") (pinfunction "2_2") (pintype "passive"))
      (node (ref "C257") (pin "1") (pinfunction "1_1") (pintype "passive"))
      (node (ref "C258") (pin "2") (pinfunction "2_2") (pintype "passive"))
      (node (ref "D32") (pin "3") (pinfunction "GND_3") (pintype "power_in"))
      (node (ref "D32") (pin "8") (pinfunction "GND_8") (pintype "power_in"))
      (node (ref "D33") (pin "3") (pinfunction "GND_3") (pintype "power_in"))
      (node (ref "D33") (pin "8") (pinfunction "GND_8") (pintype "power_in"))
      (node (ref "D34") (pin "3") (pinfunction "GND_3") (pintype "power_in"))
      (node (ref "D34") (pin "8") (pinfunction "GND_8") (pintype "power_in"))
      (node (ref "J6") (pin "11") (pinfunction "11_11") (pintype "passive"))
      (node (ref "J6") (pin "17") (pinfunction "17_17") (pintype "passive"))
      (node (ref "J6") (pin "2") (pinfunction "2_2") (pintype "passive"))
      (node (ref "J6") (pin "20") (pinfunction "MNT_1_20") (pintype "passive"))
      (node (ref "J6") (pin "21") (pinfunction "MNT_2_21") (pintype "passive"))
      (node (ref "J6") (pin "22") (pinfunction "MNT_3_22") (pintype "passive"))
      (node (ref "J6") (pin "5") (pinfunction "5_5") (pintype "passive"))
      (node (ref "J6") (pin "8") (pinfunction "8_8") (pintype "passive"))
      (node (ref "Q2") (pin "2") (pinfunction "S_2") (pintype "passive"))
      (node (ref "Q5") (pin "2") (pinfunction "S_2") (pintype "passive"))
      (node (ref "R281") (pin "1") (pinfunction "1_1") (pintype "passive"))
      (node (ref "R282") (pin "2") (pinfunction "2_2") (pintype "passive"))
      (node (ref "R285") (pin "1") (pinfunction "1_1") (pintype "passive"))
      (node (ref "R286") (pin "2") (pinfunction "2_2") (pintype "passive"))
      (node (ref "R76") (pin "1") (pinfunction "1_1") (pintype "passive"))
      (node (ref "R93") (pin "1") (pinfunction "1_1") (pintype "passive"))
    )
    (net (code "41") (name "JETSON_1V8_REF") (class "Default")
      (node (ref "R287") (pin "1") (pinfunction "1_1") (pintype "passive"))
    )
    (net (code "42") (name "Net-(C114-Pad2)") (class "Default")
      (node (ref "C114") (pin "2") (pinfunction "2_2") (pintype "passive"))
      (node (ref "R73") (pin "2") (pinfunction "2_2") (pintype "passive"))
      (node (ref "R74") (pin "1") (pinfunction "1_1") (pintype "passive"))
    )
    (net (code "43") (name "Net-(D35-A2)") (class "Default")
      (node (ref "D35") (pin "2") (pinfunction "A2_2") (pintype "passive"))
      (node (ref "R96") (pin "1") (pinfunction "1_1") (pintype "passive"))
    )
    (net (code "44") (name "Net-(D35-K)") (class "Default")
      (node (ref "D35") (pin "3") (pinfunction "K_3") (pintype "passive"))
      (node (ref "Q6") (pin "3") (pinfunction "D_3") (pintype "passive"))
      (node (ref "R95") (pin "1") (pinfunction "1_1") (pintype "passive"))
    )
    (net (code "45") (name "Net-(FB1-Pad2)") (class "Default")
      (node (ref "FB1") (pin "2") (pinfunction "2_2") (pintype "passive"))
      (node (ref "R77") (pin "2") (pinfunction "2_2") (pintype "passive"))
    )
    (net (code "46") (name "Net-(FB2-Pad2)") (class "Default")
      (node (ref "FB2") (pin "2") (pinfunction "2_2") (pintype "passive"))
      (node (ref "R78") (pin "2") (pinfunction "2_2") (pintype "passive"))
    )
    (net (code "47") (name "Net-(FB3-Pad2)") (class "Default")
      (node (ref "FB3") (pin "2") (pinfunction "2_2") (pintype "passive"))
      (node (ref "R79") (pin "2") (pinfunction "2_2") (pintype "passive"))
    )
    (net (code "48") (name "Net-(FB4-Pad2)") (class "Default")
      (node (ref "FB4") (pin "2") (pinfunction "2_2") (pintype "passive"))
      (node (ref "R82") (pin "2") (pinfunction "2_2") (pintype "passive"))
    )
    (net (code "49") (name "Net-(FB5-Pad2)") (class "Default")
      (node (ref "FB5") (pin "2") (pinfunction "2_2") (pintype "passive"))
      (node (ref "R84") (pin "2") (pinfunction "2_2") (pintype "passive"))
    )
    (net (code "50") (name "Net-(FB6-Pad2)") (class "Default")
      (node (ref "FB6") (pin "2") (pinfunction "2_2") (pintype "passive"))
      (node (ref "R85") (pin "2") (pinfunction "2_2") (pintype "passive"))
    )
    (net (code "51") (name "Net-(FB7-Pad2)") (class "Default")
      (node (ref "FB7") (pin "2") (pinfunction "2_2") (pintype "passive"))
      (node (ref "R86") (pin "2") (pinfunction "2_2") (pintype "passive"))
    )
    (net (code "52") (name "Net-(FB8-Pad2)") (class "Default")
      (node (ref "FB8") (pin "2") (pinfunction "2_2") (pintype "passive"))
      (node (ref "R87") (pin "2") (pinfunction "2_2") (pintype "passive"))
    )
    (net (code "53") (name "Net-(Q2-G)") (class "Default")
      (node (ref "Q2") (pin "1") (pinfunction "G_1") (pintype "passive"))
      (node (ref "R73") (pin "1") (pinfunction "1_1") (pintype "passive"))
      (node (ref "R76") (pin "2") (pinfunction "2_2") (pintype "passive"))
    )
    (net (code "54") (name "Net-(Q3-D)") (class "Default")
      (node (ref "C117") (pin "1") (pinfunction "1_1") (pintype "passive"))
      (node (ref "Q3") (pin "3") (pinfunction "D_3") (pintype "passive"))
      (node (ref "R81") (pin "1") (pinfunction "1_1") (pintype "passive"))
      (node (ref "R83") (pin "1") (pinfunction "1_1") (pintype "passive"))
    )
    (net (code "55") (name "Net-(Q4-D)") (class "Default")
      (node (ref "C258") (pin "1") (pinfunction "1_1") (pintype "passive"))
      (node (ref "Q4") (pin "3") (pinfunction "D_3") (pintype "passive"))
      (node (ref "R89") (pin "1") (pinfunction "1_1") (pintype "passive"))
      (node (ref "R90") (pin "1") (pinfunction "1_1") (pintype "passive"))
    )
    (net (code "56") (name "Net-(Q5-D)") (class "Default")
      (node (ref "FB1") (pin "1") (pinfunction "1_1") (pintype "passive"))
      (node (ref "FB2") (pin "1") (pinfunction "1_1") (pintype "passive"))
      (node (ref "FB3") (pin "1") (pinfunction "1_1") (pintype "passive"))
      (node (ref "FB4") (pin "1") (pinfunction "1_1") (pintype "passive"))
      (node (ref "FB5") (pin "1") (pinfunction "1_1") (pintype "passive"))
      (node (ref "FB6") (pin "1") (pinfunction "1_1") (pintype "passive"))
      (node (ref "FB7") (pin "1") (pinfunction "1_1") (pintype "passive"))
      (node (ref "FB8") (pin "1") (pinfunction "1_1") (pintype "passive"))
      (node (ref "Q5") (pin "3") (pinfunction "D_3") (pintype "passive"))
    )
    (net (code "57") (name "Net-(Q6-G)") (class "Default")
      (node (ref "Q6") (pin "1") (pinfunction "G_1") (pintype "passive"))
      (node (ref "R279") (pin "2") (pinfunction "2_2") (pintype "passive"))
      (node (ref "R94") (pin "2") (pinfunction "2_2") (pintype "passive"))
    )
    (net (code "58") (name "Net-(U10-R1{slash}C1_(PU))") (class "Default")
      (node (ref "R280") (pin "1") (pinfunction "1_1") (pintype "passive"))
      (node (ref "U10") (pin "6") (pinfunction "R1/C1_(PU)_6") (pintype "passive"))
    )
    (net (code "59") (name "Net-(U10-R2_(PD))") (class "Default")
      (node (ref "R282") (pin "1") (pinfunction "1_1") (pintype "passive"))
      (node (ref "U10") (pin "1") (pinfunction "R2_(PD)_1") (pintype "passive"))
    )
    (net (code "60") (name "Net-(U31-ON{slash}OFF_(TRIG))") (class "Default")
      (node (ref "R284") (pin "2") (pinfunction "2_2") (pintype "passive"))
      (node (ref "R285") (pin "2") (pinfunction "2_2") (pintype "passive"))
      (node (ref "U31") (pin "5") (pinfunction "ON/OFF_(TRIG)_5") (pintype "passive"))
    )
    (net (code "61") (name "Net-(U31-R1{slash}C1_(PU))") (class "Default")
      (node (ref "R283") (pin "1") (pinfunction "1_1") (pintype "passive"))
      (node (ref "U31") (pin "6") (pinfunction "R1/C1_(PU)_6") (pintype "passive"))
    )
    (net (code "62") (name "Net-(U31-R2_(PD))") (class "Default")
      (node (ref "R286") (pin "1") (pinfunction "1_1") (pintype "passive"))
      (node (ref "U31") (pin "1") (pinfunction "R2_(PD)_1") (pintype "passive"))
    )
    (net (code "63") (name "unconnected-(J6-Pad14)") (class "Default")
      (node (ref "J6") (pin "14") (pinfunction "14_14") (pintype "passive+no_connect"))
    )
  )
)
